# privado.net
KiCad netlist of a schematic drawn in Altium Designer
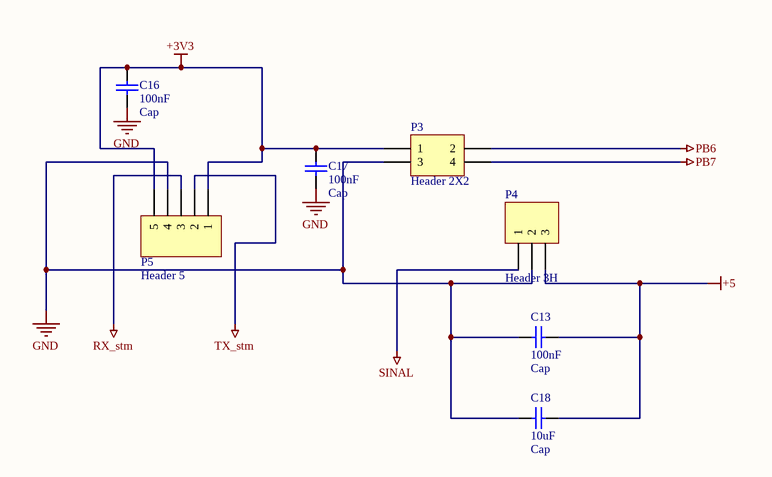
[diagram p0: privado.SchDoc]

(export (version "E")
  (design (tool "Eeschema 10.0.6"))
  (components
    (comp (ref "C13")
      (value "Cap")
      (footprint "lib_footprint_projeto:CAP100N")
      (description "Capacitor")
      (fields (field (name "ALTIUM_VALUE") "100nF") (field (name "PUBLISHER") "Altium Limited"))
      (libsource (lib "Miscellaneous Devices") (part "Cap"))
    )
    (comp (ref "C16")
      (value "Cap")
      (footprint "lib_footprint_projeto:CAP100N")
      (description "Capacitor")
      (fields (field (name "ALTIUM_VALUE") "100nF") (field (name "PUBLISHER") "Altium Limited"))
      (libsource (lib "Miscellaneous Devices") (part "Cap"))
    )
    (comp (ref "C17")
      (value "Cap")
      (footprint "lib_footprint_projeto:CAP100N")
      (description "Capacitor")
      (fields (field (name "ALTIUM_VALUE") "100nF") (field (name "PUBLISHER") "Altium Limited"))
      (libsource (lib "Miscellaneous Devices") (part "Cap"))
    )
    (comp (ref "C18")
      (value "Cap")
      (footprint "lib_footprint_projeto:CAP10uF")
      (description "Capacitor")
      (fields (field (name "ALTIUM_VALUE") "10uF") (field (name "PUBLISHER") "Altium Limited"))
      (libsource (lib "Miscellaneous Devices") (part "Cap"))
    )
    (comp (ref "P3")
      (value "Header 2X2")
      (footprint "lib_footprint_projeto:Borne 4 vias")
      (description "Header, 2-Pin, Dual row")
      (fields (field (name "PUBLISHER") "Altium Limited"))
      (libsource (lib "Miscellaneous Connectors") (part "Header 2X2"))
    )
    (comp (ref "P4")
      (value "Header 3H")
      (footprint "lib_footprint_projeto:borne 3 vias")
      (description "Header, 3-Pin, Right Angle")
      (fields (field (name "PUBLISHER") "Altium Limited"))
      (libsource (lib "Miscellaneous Connectors") (part "Header 3H"))
    )
    (comp (ref "P5")
      (value "Header 5")
      (footprint "lib_footprint_projeto:Borne 5 vias")
      (description "Header, 5-Pin")
      (fields (field (name "PUBLISHER") "Altium Limited"))
      (libsource (lib "Miscellaneous Connectors") (part "Header 5"))
    )
  )
  (nets
    (net (code "1") (name "+3V3") (class "Default")
      (node (ref "C16") (pin "2") (pinfunction "2_2") (pintype "passive"))
      (node (ref "C17") (pin "2") (pinfunction "2_2") (pintype "passive"))
      (node (ref "P3") (pin "1") (pinfunction "1_1") (pintype "passive"))
      (node (ref "P5") (pin "1") (pinfunction "1_1") (pintype "passive"))
      (node (ref "P5") (pin "5") (pinfunction "5_5") (pintype "passive"))
    )
    (net (code "2") (name "+5") (class "Default")
      (node (ref "C13") (pin "2") (pinfunction "2_2") (pintype "passive"))
      (node (ref "C18") (pin "2") (pinfunction "2_2") (pintype "passive"))
      (node (ref "P4") (pin "3") (pinfunction "3_3") (pintype "passive"))
    )
    (net (code "3") (name "GND") (class "Default")
      (node (ref "C13") (pin "1") (pinfunction "1_1") (pintype "passive"))
      (node (ref "C16") (pin "1") (pinfunction "1_1") (pintype "passive"))
      (node (ref "C17") (pin "1") (pinfunction "1_1") (pintype "passive"))
      (node (ref "C18") (pin "1") (pinfunction "1_1") (pintype "passive"))
      (node (ref "P3") (pin "3") (pinfunction "3_3") (pintype "passive"))
      (node (ref "P4") (pin "2") (pinfunction "2_2") (pintype "passive"))
      (node (ref "P5") (pin "4") (pinfunction "4_4") (pintype "passive"))
    )
    (net (code "4") (name "PB6") (class "Default")
      (node (ref "P3") (pin "2") (pinfunction "2_2") (pintype "passive"))
    )
    (net (code "5") (name "PB7") (class "Default")
      (node (ref "P3") (pin "4") (pinfunction "4_4") (pintype "passive"))
    )
    (net (code "6") (name "RX_stm") (class "Default")
      (node (ref "P5") (pin "3") (pinfunction "3_3") (pintype "passive"))
    )
    (net (code "7") (name "SINAL") (class "Default")
      (node (ref "P4") (pin "1") (pinfunction "1_1") (pintype "passive"))
    )
    (net (code "8") (name "TX_stm") (class "Default")
      (node (ref "P5") (pin "2") (pinfunction "2_2") (pintype "passive"))
    )
  )
)
